# 5mm_front_end.net
KiCad netlist of a schematic drawn in EAGLE
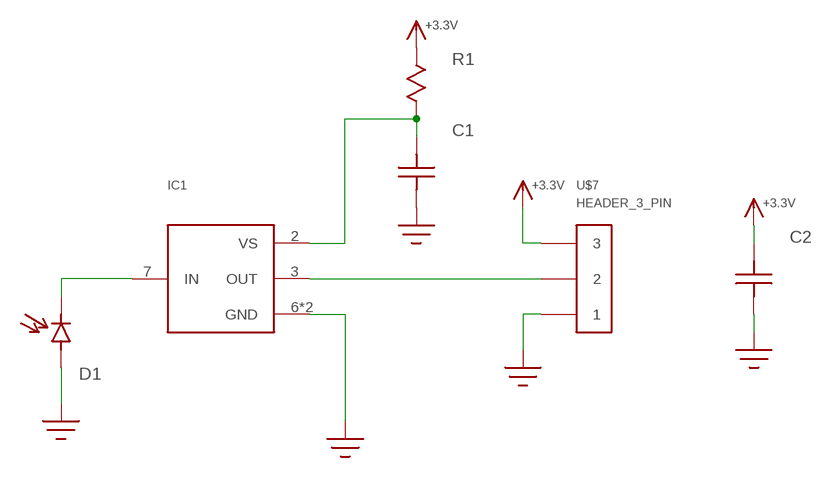
[diagram p0: schematic, sheet 1]

(export (version "E")
  (design (tool "Eeschema 10.0.6"))
  (components
    (comp (ref "C1")
      (value "C0603")
      (footprint "eagle-import:C0603")
      (libsource (lib "eagle-import") (part "C0603"))
    )
    (comp (ref "C2")
      (value "C0805")
      (footprint "eagle-import:0805")
      (libsource (lib "eagle-import") (part "C0805"))
    )
    (comp (ref "D1")
      (value "PHOTODIODE")
      (footprint "eagle-import:LED_RA_5MM")
      (libsource (lib "eagle-import") (part "PHOTODIODE"))
    )
    (comp (ref "IC1")
      (value "VSOP98260")
      (footprint "eagle-import:VSOP98260")
      (libsource (lib "eagle-import") (part "VSOP98260"))
    )
    (comp (ref "R1")
      (value "R0603")
      (footprint "eagle-import:R0603")
      (libsource (lib "eagle-import") (part "R0603"))
    )
    (comp (ref "U$7")
      (value "HEADER_3_PIN")
      (footprint "eagle-import:HEADER_3_PIN")
      (libsource (lib "eagle-import") (part "HEADER_3_PIN"))
    )
  )
  (nets
    (net (code "1") (name "+3.3V") (class "Default")
      (node (ref "C2") (pin "P$2") (pinfunction "P$2_P$2") (pintype "bidirectional"))
      (node (ref "R1") (pin "P$1") (pinfunction "P$3_P$1") (pintype "bidirectional"))
      (node (ref "U$7") (pin "3") (pinfunction "3_3") (pintype "bidirectional"))
    )
    (net (code "2") (name "GND") (class "Default")
      (node (ref "C1") (pin "P$1") (pinfunction "P$1_P$1") (pintype "bidirectional"))
      (node (ref "C2") (pin "P$1") (pinfunction "P$1_P$1") (pintype "bidirectional"))
      (node (ref "D1") (pin "A") (pinfunction "A_A") (pintype "bidirectional"))
      (node (ref "IC1") (pin "6") (pinfunction "GND_6") (pintype "bidirectional"))
      (node (ref "IC1") (pin "8") (pinfunction "GND_8") (pintype "bidirectional"))
      (node (ref "U$7") (pin "1") (pinfunction "1_1") (pintype "bidirectional"))
    )
    (net (code "3") (name "Net-(IC1-IN)") (class "Default")
      (node (ref "D1") (pin "C") (pinfunction "C_C") (pintype "bidirectional"))
      (node (ref "IC1") (pin "7") (pinfunction "IN_7") (pintype "bidirectional"))
    )
    (net (code "4") (name "Net-(IC1-OUT)") (class "Default")
      (node (ref "IC1") (pin "3") (pinfunction "OUT_3") (pintype "bidirectional"))
      (node (ref "U$7") (pin "2") (pinfunction "2_2") (pintype "bidirectional"))
    )
    (net (code "5") (name "Net-(IC1-VS)") (class "Default")
      (node (ref "C1") (pin "P$2") (pinfunction "P$2_P$2") (pintype "bidirectional"))
      (node (ref "IC1") (pin "2") (pinfunction "VS_2") (pintype "bidirectional"))
      (node (ref "R1") (pin "P$2") (pinfunction "P$4_P$2") (pintype "bidirectional"))
    )
  )
)
